# POWER_SUPPLY.net
KiCad netlist of a schematic drawn in Altium Designer
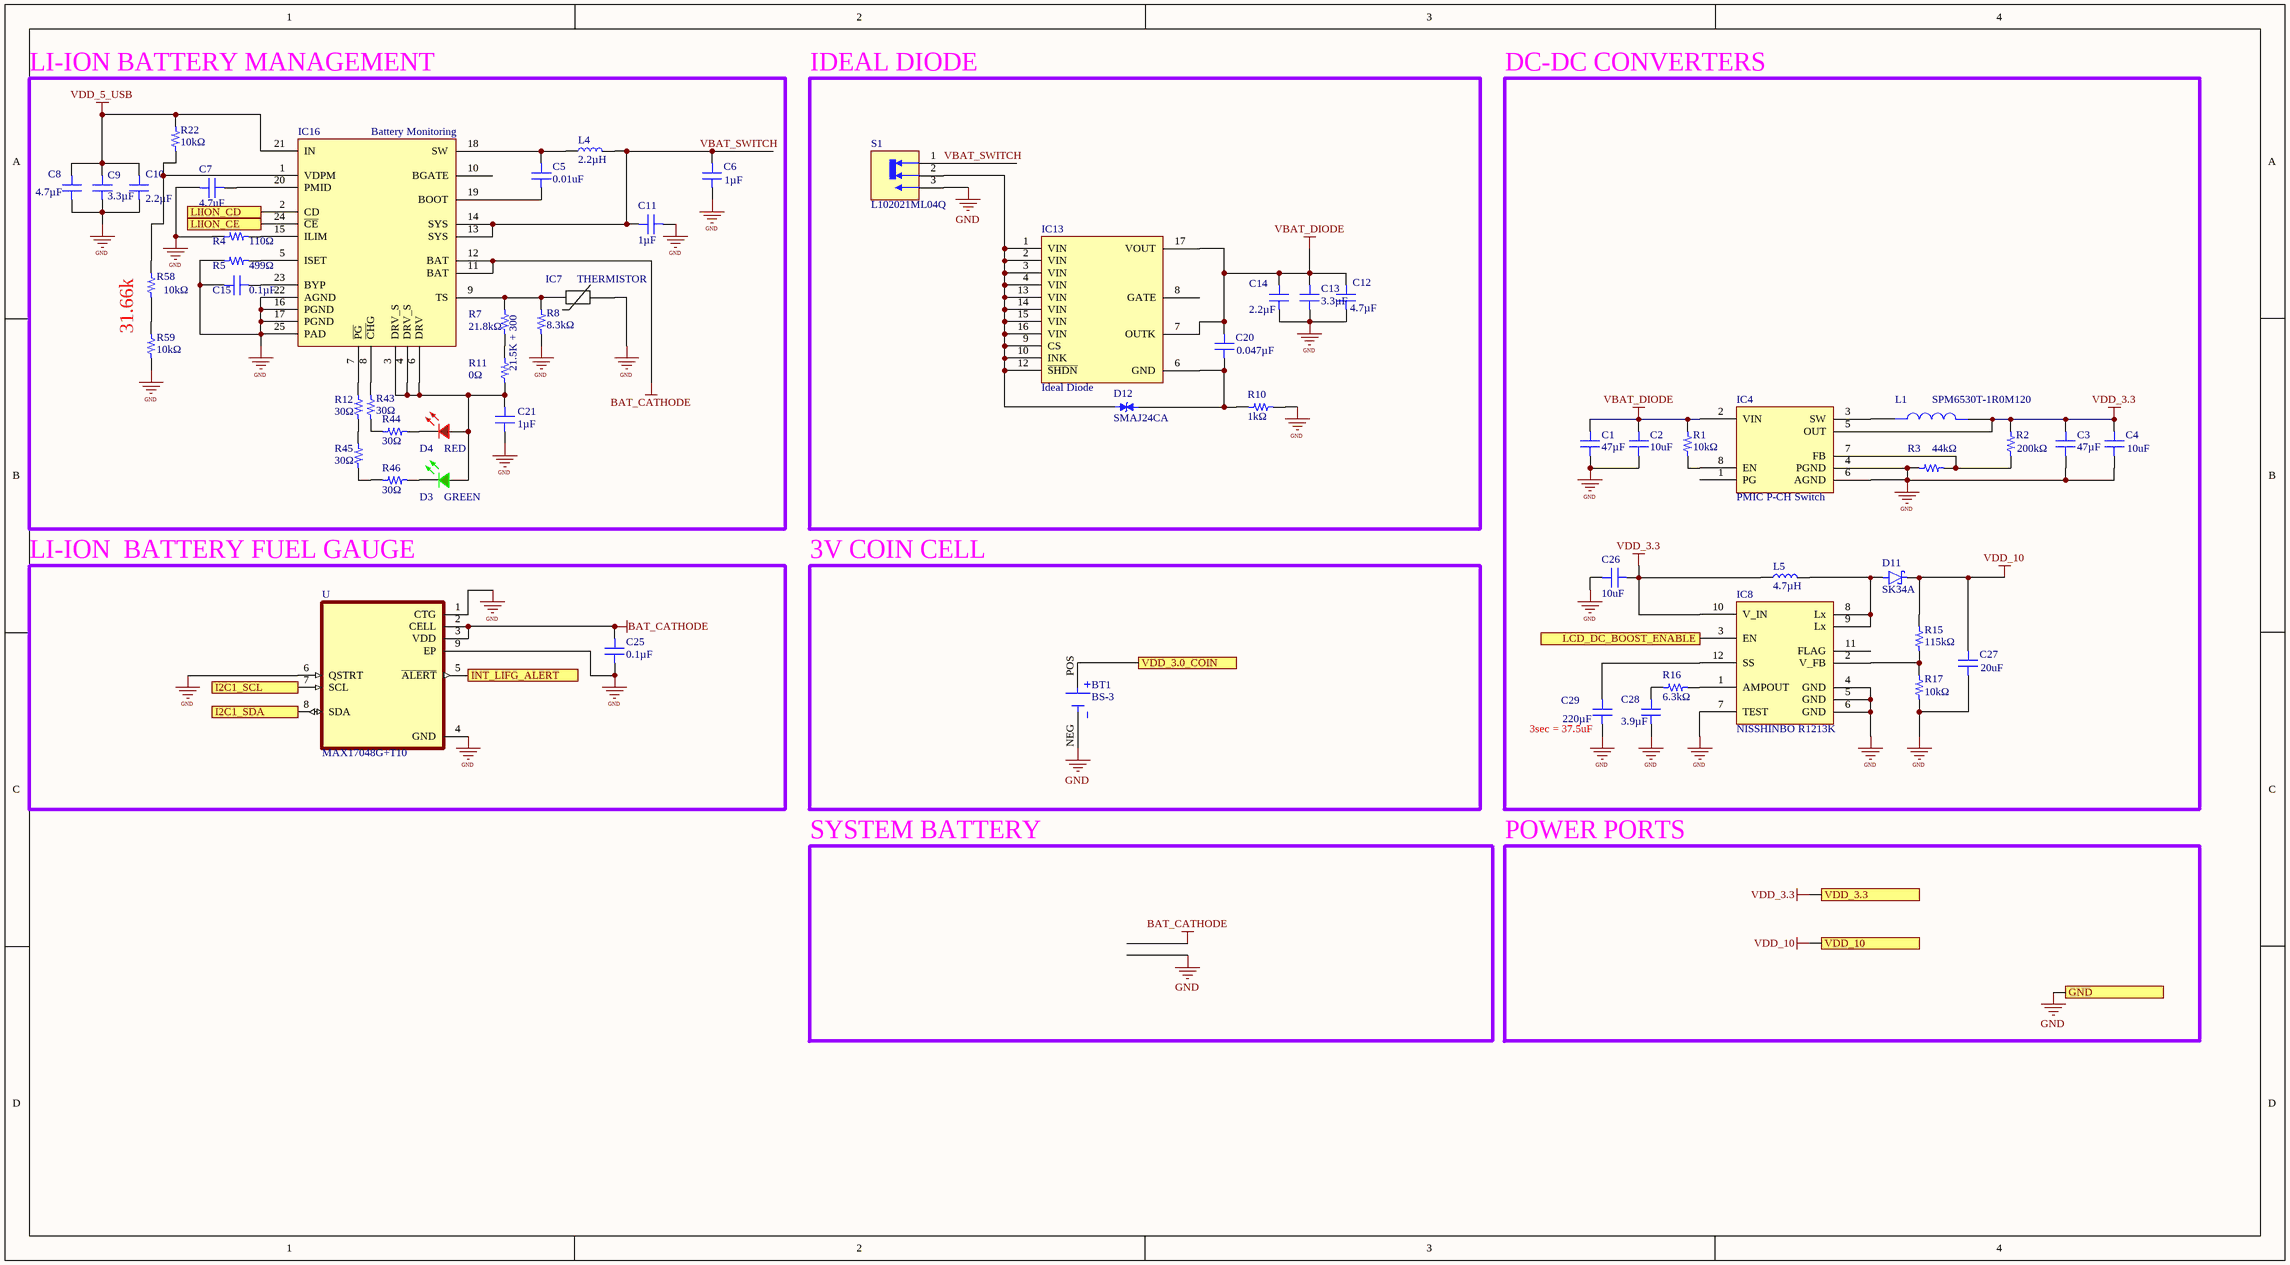
[diagram p0: POWER SUPPLY.SchDoc]

(export (version "E")
  (design (tool "Eeschema 10.0.6"))
  (components
    (comp (ref "BT1")
      (value "BS-3")
      (footprint "BAT_BS-3")
      (description "Holder Coincell 2032 Retainr Arm")
      (fields (field (name "MF") "MPD (Memory"))
      (libsource (lib "BS-3") (part "BS-3"))
    )
    (comp (ref "C1")
      (value "47µF")
      (footprint "CAP 1210_3225 - 2.2MM")
      (description "CAP CER 47UF 10V X7R 1210")
      (fields (field (name "MANUFACTURER") "Murata Electronics") (field (name "VOLTAGE") "10V"))
      (libsource (lib "MVVVMAltiumDatabase") (part "Capacitor"))
    )
    (comp (ref "C2")
      (value "10uF")
      (footprint "CAP 0603_1608")
      (description "CAP CER 10UF 6.3V X7R 0603")
      (fields (field (name "MANUFACTURER") "TDK") (field (name "VOLTAGE") "6.3V"))
      (libsource (lib "MVVVMAltiumDatabase") (part "Capacitor"))
    )
    (comp (ref "C3")
      (value "47µF")
      (footprint "CAP 1210_3225 - 2.2MM")
      (description "CAP CER 47UF 10V X7R 1210")
      (fields (field (name "MANUFACTURER") "Murata Electronics") (field (name "VOLTAGE") "10V"))
      (libsource (lib "MVVVMAltiumDatabase") (part "Capacitor"))
    )
    (comp (ref "C4")
      (value "10uF")
      (footprint "CAP 0603_1608")
      (description "CAP CER 10UF 6.3V X7R 0603")
      (fields (field (name "MANUFACTURER") "TDK") (field (name "VOLTAGE") "6.3V"))
      (libsource (lib "MVVVMAltiumDatabase") (part "Capacitor"))
    )
    (comp (ref "C5")
      (value "0.01uF")
      (footprint "CAP 0603_1608")
      (description "CAP CER 0.01UF 25V X7R 0603")
      (fields (field (name "MANUFACTURER") "TDK") (field (name "VOLTAGE") "25V"))
      (libsource (lib "MVVVMAltiumDatabase") (part "Capacitor"))
    )
    (comp (ref "C6")
      (value "1µF")
      (footprint "CAP 0603_1608")
      (description "CAP CER 1UF 10V X7R 0603")
      (fields (field (name "MANUFACTURER") "KEMET") (field (name "VOLTAGE") "10V"))
      (libsource (lib "MVVVMAltiumDatabase") (part "Capacitor"))
    )
    (comp (ref "C7")
      (value "4.7uF")
      (footprint "CAP 0603_1608")
      (description "CAP CER 4.7UF 50V X7R 0603")
      (fields (field (name "MANUFACTURER") "KEMET") (field (name "VOLTAGE") "25V"))
      (libsource (lib "MVVVMAltiumDatabase") (part "Capacitor"))
    )
    (comp (ref "C8")
      (value "4.7µF")
      (footprint "CAP 0805_2012")
      (description "CAP CER 4.7UF 16V X7R 0805")
      (fields (field (name "MANUFACTURER") "KEMET") (field (name "VOLTAGE") "16V"))
      (libsource (lib "MVVVMAltiumDatabase") (part "Capacitor"))
    )
    (comp (ref "C9")
      (value "3.3µF")
      (footprint "0805_2012 RF")
      (description "CAP CER 3.3UF 16V X7R 0805")
      (fields (field (name "MANUFACTURER") "KEMET") (field (name "VOLTAGE") "16V"))
      (libsource (lib "MVVVMAltiumDatabase") (part "Capacitor"))
    )
    (comp (ref "C10")
      (value "2.2µF")
      (footprint "CAP 0603_1608")
      (description "CAP CER 2.2UF 10V X7R 0603")
      (fields (field (name "MANUFACTURER") "KEMET") (field (name "VOLTAGE") "10V"))
      (libsource (lib "MVVVMAltiumDatabase") (part "Capacitor"))
    )
    (comp (ref "C11")
      (value "1µF")
      (footprint "CAP 0603_1608")
      (description "CAP CER 1UF 10V X7R 0603")
      (fields (field (name "MANUFACTURER") "KEMET") (field (name "VOLTAGE") "10V"))
      (libsource (lib "MVVVMAltiumDatabase") (part "Capacitor"))
    )
    (comp (ref "C12")
      (value "4.7µF")
      (footprint "CAP 0805_2012")
      (description "CAP CER 4.7UF 16V X7R 0805")
      (fields (field (name "MANUFACTURER") "KEMET") (field (name "VOLTAGE") "16V"))
      (libsource (lib "MVVVMAltiumDatabase") (part "Capacitor"))
    )
    (comp (ref "C13")
      (value "3.3µF")
      (footprint "0805_2012 RF")
      (description "CAP CER 3.3UF 16V X7R 0805")
      (fields (field (name "MANUFACTURER") "KEMET") (field (name "VOLTAGE") "16V"))
      (libsource (lib "MVVVMAltiumDatabase") (part "Capacitor"))
    )
    (comp (ref "C14")
      (value "2.2µF")
      (footprint "CAP 0603_1608")
      (description "CAP CER 2.2UF 10V X7R 0603")
      (fields (field (name "MANUFACTURER") "KEMET") (field (name "VOLTAGE") "10V"))
      (libsource (lib "MVVVMAltiumDatabase") (part "Capacitor"))
    )
    (comp (ref "C15")
      (value "0.1µF")
      (footprint "CAP 0603_1608 RF")
      (description "CAP CER 0.1UF 16V X7R 0603")
      (fields (field (name "MANUFACTURER") "KEMET") (field (name "VOLTAGE") "16V"))
      (libsource (lib "MVVVMAltiumDatabase") (part "Capacitor"))
    )
    (comp (ref "C20")
      (value "0.047µF")
      (footprint "CAP 0603_1608")
      (description "CAP CER 0.047UF 50V X7R 0603")
      (fields (field (name "MANUFACTURER") "KEMET") (field (name "VOLTAGE") "50V"))
      (libsource (lib "MVVVMAltiumDatabase") (part "Capacitor"))
    )
    (comp (ref "C21")
      (value "1µF")
      (footprint "CAP 0603_1608")
      (description "CAP CER 1UF 10V X7R 0603")
      (fields (field (name "MANUFACTURER") "KEMET") (field (name "VOLTAGE") "10V"))
      (libsource (lib "MVVVMAltiumDatabase") (part "Capacitor"))
    )
    (comp (ref "C25")
      (value "0.1µF")
      (footprint "CAP 0603_1608 RF")
      (description "CAP CER 0.1UF 16V X7R 0603")
      (fields (field (name "MANUFACTURER") "KEMET") (field (name "VOLTAGE") "16V"))
      (libsource (lib "MVVVMAltiumDatabase") (part "Capacitor"))
    )
    (comp (ref "C26")
      (value "10uF")
      (footprint "CAP 0603_1608")
      (description "CAP CER 10UF 6.3V X7R 0603")
      (fields (field (name "MANUFACTURER") "TDK") (field (name "VOLTAGE") "6.3V"))
      (libsource (lib "MVVVMAltiumDatabase") (part "Capacitor"))
    )
    (comp (ref "C27")
      (value "20uF")
      (footprint "CAP 0603_1608")
      (description "CAP CER 20UF 25V X7R 0603")
      (fields (field (name "MANUFACTURER") "TDK") (field (name "VOLTAGE") "25V"))
      (libsource (lib "MVVVMAltiumDatabase") (part "Capacitor"))
    )
    (comp (ref "C28")
      (value "3.9µF")
      (footprint "CAP 0805_2012")
      (description "CAP CER 3.9UF 50V X7R 0805")
      (fields (field (name "MANUFACTURER") "KEMET") (field (name "VOLTAGE") "50V"))
      (libsource (lib "MVVVMAltiumDatabase") (part "Capacitor"))
    )
    (comp (ref "C29")
      (value "220µF")
      (footprint "CAP 0805_2012")
      (description "CAP CER 220UF 50V X7R 0805")
      (fields (field (name "MANUFACTURER") "KEMET") (field (name "VOLTAGE") "50V"))
      (libsource (lib "MVVVMAltiumDatabase") (part "Capacitor"))
    )
    (comp (ref "D3")
      (value "GREEN")
      (footprint "LED 0603_1608")
      (description "LED RED CLEAR 0603 SMD")
      (fields (field (name "MANUFACTURER") "Würth Elektronik"))
      (libsource (lib "MVVVMAltiumDatabase") (part "LED_GREEN"))
    )
    (comp (ref "D4")
      (value "RED")
      (footprint "LED 0603_1608")
      (description "LED RED CLEAR 0603 SMD")
      (fields (field (name "MANUFACTURER") "Würth Elektronik"))
      (libsource (lib "MVVVMAltiumDatabase") (part "LED_RED"))
    )
    (comp (ref "D11") (value "SK34A") (footprint "DIOM4325X250N") (libsource (lib "SK34A") (part "SK34A")))
    (comp (ref "D12")
      (value "SMAJ24CA")
      (footprint "DIOM4325X250N")
      (libsource (lib "SMAJ24CA") (part "SMAJ24CA"))
    )
    (comp (ref "IC4")
      (value "PMIC P-CH Switch")
      (footprint "MPS MP2144 TSOT23-8")
      (description "IC PWR SWITCH P-CHAN 1:1 4TDFN")
      (fields (field (name "MANUFACTURER") "Vishay Siliconix"))
      (libsource (lib "MVVVMAltiumDatabase") (part "MPS MP2144"))
    )
    (comp (ref "IC7")
      (value "THERMISTOR")
      (footprint "THERMISTOR 2TH")
      (description "10kΩ THERMISTOR 0603")
      (fields (field (name "MANUFACTURER") "Texas Instruments"))
      (libsource (lib "MVVVMAltiumDatabase") (part "THERMISTOR"))
    )
    (comp (ref "IC8")
      (value "NISSHINBO R1213K")
      (footprint "NISSHINBO R1213K")
      (description "IC REG CONV BLUETTH 1OUT 12WSON")
      (fields (field (name "MANUFACTURER") "Texas Instruments"))
      (libsource (lib "MVVVMAltiumDatabase") (part "NISSHINBO R1213K"))
    )
    (comp (ref "IC13")
      (value "Ideal Diode")
      (footprint "ANALOG DFN-16")
      (description "IC OR CTRLR IDEAL DIODE SC70-6")
      (fields (field (name "MANUFACTURER") "Texas Instruments"))
      (libsource (lib "MVVVMAltiumDatabase") (part "ANALOG LTC4376"))
    )
    (comp (ref "IC16")
      (value "Battery Monitoring")
      (footprint "TI BQ24278")
      (description "IC BATT MON LI-ION 1CELL 24QFN")
      (fields (field (name "MANUFACTURER") "Analog Devices Inc."))
      (libsource (lib "MVVVMAltiumDatabase") (part "TI BQ24278"))
    )
    (comp (ref "L1")
      (value "SPM6530T-1R0M120")
      (footprint "IND_SPM6530T-1R0M120")
      (description "1 ÂµH Shielded Drum Core, Wirewound Inductor 13 A 7.81mOhm Max Nonstandard")
      (fields (field (name "MF") "TDK"))
      (libsource (lib "SPM6530T-1R0M120") (part "SPM6530T-1R0M120"))
    )
    (comp (ref "L4")
      (value "2.2µH")
      (footprint "IND 0806_2016")
      (description "FIXED IND 2.2UH 1.8A 139 MOHM")
      (fields (field (name "MANUFACTURER") "Samsung Electro-Mechanics") (field (name "TOLERANCE") "±20%"))
      (libsource (lib "MVVVMAltiumDatabase") (part "Inductor_2"))
    )
    (comp (ref "L5")
      (value "4.7µH")
      (footprint "NTC 0603_1608")
      (description "FIXED IND 4.7UH 16V")
      (fields (field (name "MANUFACTURER") "TDK Corporation") (field (name "TOLERANCE") "±20%"))
      (libsource (lib "MVVVMAltiumDatabase") (part "Inductor_2"))
    )
    (comp (ref "R1")
      (value "10kΩ")
      (footprint "RES 0603_1608 RF")
      (description "RES 10k OHM 1% 1/10W 0603")
      (fields (field (name "MANUFACTURER") "Vishay Dale") (field (name "TOLERANCE") "±1%"))
      (libsource (lib "MVVVMAltiumDatabase") (part "Resistor"))
    )
    (comp (ref "R2")
      (value "200kΩ")
      (footprint "RES 0603_1608 RF")
      (description "RES 200k OHM 1% 1/10W 0603")
      (fields (field (name "MANUFACTURER") "Vishay Dale") (field (name "TOLERANCE") "±1%"))
      (libsource (lib "MVVVMAltiumDatabase") (part "Resistor"))
    )
    (comp (ref "R3")
      (value "44kΩ")
      (footprint "RES 0603_1608 RF")
      (description "RES 44k OHM 1% 1/10W 0603")
      (fields (field (name "MANUFACTURER") "Vishay Dale") (field (name "TOLERANCE") "±1%"))
      (libsource (lib "MVVVMAltiumDatabase") (part "Resistor"))
    )
    (comp (ref "R4")
      (value "110Ω")
      (footprint "RES 0603_1608 RF")
      (description "RES 110 OHM 1% 1/10W 0603")
      (fields (field (name "MANUFACTURER") "Vishay Dale") (field (name "TOLERANCE") "±1%"))
      (libsource (lib "MVVVMAltiumDatabase") (part "Resistor"))
    )
    (comp (ref "R5")
      (value "499Ω")
      (footprint "RES 0603_1608 RF")
      (description "RES SMD 499 OHM 1% 1/10W 0603")
      (fields (field (name "MANUFACTURER") "Vishay Dale") (field (name "TOLERANCE") "±1%"))
      (libsource (lib "MVVVMAltiumDatabase") (part "Resistor"))
    )
    (comp (ref "R7")
      (value "21.8kΩ")
      (footprint "RES 0603_1608 RF")
      (description "RES 21.8k OHM 1% 1/10W 0603")
      (fields (field (name "MANUFACTURER") "Vishay Dale") (field (name "TOLERANCE") "±1%"))
      (libsource (lib "MVVVMAltiumDatabase") (part "Resistor"))
    )
    (comp (ref "R8")
      (value "8.3kΩ")
      (footprint "RES 0603_1608 RF")
      (description "RES 8.3k OHM 1% 1/10W 0603")
      (fields (field (name "MANUFACTURER") "Vishay Dale") (field (name "TOLERANCE") "±1%"))
      (libsource (lib "MVVVMAltiumDatabase") (part "Resistor"))
    )
    (comp (ref "R10")
      (value "1kΩ")
      (footprint "RES 0603_1608 RF")
      (description "RES SMD 1K OHM 0.1% 1/10W 0603")
      (fields (field (name "MANUFACTURER") "Susumu") (field (name "TOLERANCE") "±0.1%"))
      (libsource (lib "MVVVMAltiumDatabase") (part "Resistor"))
    )
    (comp (ref "R11")
      (value "0Ω")
      (footprint "RES 0603_1608 RF")
      (description "RES 0 OHM 1% 1/10W 0603")
      (fields (field (name "MANUFACTURER") "Vishay Dale") (field (name "TOLERANCE") "±1%"))
      (libsource (lib "MVVVMAltiumDatabase") (part "Resistor"))
    )
    (comp (ref "R12")
      (value "30Ω")
      (footprint "RES 0603_1608 RF")
      (description "RES 30 OHM 1% 1/10W 0603")
      (fields (field (name "MANUFACTURER") "Vishay Dale") (field (name "TOLERANCE") "±1%"))
      (libsource (lib "MVVVMAltiumDatabase") (part "Resistor"))
    )
    (comp (ref "R15")
      (value "115kΩ")
      (footprint "RES 0603_1608 RF")
      (description "RES 115k OHM 1% 1/10W 0603")
      (fields (field (name "MANUFACTURER") "Vishay Dale") (field (name "TOLERANCE") "±1%"))
      (libsource (lib "MVVVMAltiumDatabase") (part "Resistor"))
    )
    (comp (ref "R16")
      (value "6.3kΩ")
      (footprint "RES 0603_1608 RF")
      (description "RES 6.3k OHM 1% 1/10W 0603")
      (fields (field (name "MANUFACTURER") "Vishay Dale") (field (name "TOLERANCE") "±1%"))
      (libsource (lib "MVVVMAltiumDatabase") (part "Resistor"))
    )
    (comp (ref "R17")
      (value "10kΩ")
      (footprint "RES 0603_1608 RF")
      (description "RES 10k OHM 1% 1/10W 0603")
      (fields (field (name "MANUFACTURER") "Vishay Dale") (field (name "TOLERANCE") "±1%"))
      (libsource (lib "MVVVMAltiumDatabase") (part "Resistor"))
    )
    (comp (ref "R22")
      (value "10kΩ")
      (footprint "RES 0603_1608 RF")
      (description "RES 10k OHM 1% 1/10W 0603")
      (fields (field (name "MANUFACTURER") "Vishay Dale") (field (name "TOLERANCE") "±1%"))
      (libsource (lib "MVVVMAltiumDatabase") (part "Resistor"))
    )
    (comp (ref "R43")
      (value "30Ω")
      (footprint "RES 0603_1608 RF")
      (description "RES 30 OHM 1% 1/10W 0603")
      (fields (field (name "MANUFACTURER") "Vishay Dale") (field (name "TOLERANCE") "±1%"))
      (libsource (lib "MVVVMAltiumDatabase") (part "Resistor"))
    )
    (comp (ref "R44")
      (value "30Ω")
      (footprint "RES 0603_1608 RF")
      (description "RES 30 OHM 1% 1/10W 0603")
      (fields (field (name "MANUFACTURER") "Vishay Dale") (field (name "TOLERANCE") "±1%"))
      (libsource (lib "MVVVMAltiumDatabase") (part "Resistor"))
    )
    (comp (ref "R45")
      (value "30Ω")
      (footprint "RES 0603_1608 RF")
      (description "RES 30 OHM 1% 1/10W 0603")
      (fields (field (name "MANUFACTURER") "Vishay Dale") (field (name "TOLERANCE") "±1%"))
      (libsource (lib "MVVVMAltiumDatabase") (part "Resistor"))
    )
    (comp (ref "R46")
      (value "30Ω")
      (footprint "RES 0603_1608 RF")
      (description "RES 30 OHM 1% 1/10W 0603")
      (fields (field (name "MANUFACTURER") "Vishay Dale") (field (name "TOLERANCE") "±1%"))
      (libsource (lib "MVVVMAltiumDatabase") (part "Resistor"))
    )
    (comp (ref "R58")
      (value "10kΩ")
      (footprint "RES 0603_1608 RF")
      (description "RES 10k OHM 1% 1/10W 0603")
      (fields (field (name "MANUFACTURER") "Vishay Dale") (field (name "TOLERANCE") "±1%"))
      (libsource (lib "MVVVMAltiumDatabase") (part "Resistor"))
    )
    (comp (ref "R59")
      (value "10kΩ")
      (footprint "RES 0603_1608 RF")
      (description "RES 10k OHM 1% 1/10W 0603")
      (fields (field (name "MANUFACTURER") "Vishay Dale") (field (name "TOLERANCE") "±1%"))
      (libsource (lib "MVVVMAltiumDatabase") (part "Resistor"))
    )
    (comp (ref "S1")
      (value "L102021ML04Q")
      (footprint "SW_L102021ML04Q")
      (description "Slide Switch SPDT Through Hole, Right Angle")
      (fields (field (name "MF") "C&K"))
      (libsource (lib "L102021ML04Q") (part "L102021ML04Q"))
    )
    (comp (ref "U")
      (value "MAX17048G+T10")
      (footprint "SON50P200X200X80-9N")
      (description "Battery Battery Monitor IC Lithium-Ion 8-TDFN-EP (2x2)")
      (fields
        (field (name "MF") "Maxim Integrated")
        (field (name "DIGI-KEY_PART_NUMBER") "MAX17048G+T10CT-ND")
      )
      (libsource (lib "MAX17048G_T10") (part "MAX17048G+T10"))
    )
  )
  (nets
    (net (code "1") (name "/I2C1_SCL") (class "Default")
      (node (ref "U") (pin "7") (pinfunction "SCL_7") (pintype "input"))
    )
    (net (code "2") (name "/I2C1_SDA") (class "Default")
      (node (ref "U") (pin "8") (pinfunction "SDA_8") (pintype "bidirectional"))
    )
    (net (code "3") (name "/INT_LIFG_ALERT") (class "Default")
      (node (ref "U") (pin "5") (pinfunction "~{ALERT}_5") (pintype "output"))
    )
    (net (code "4") (name "/LCD_DC_BOOST_ENABLE") (class "Default")
      (node (ref "IC8") (pin "3") (pinfunction "EN_3") (pintype "passive"))
    )
    (net (code "5") (name "/LIION_CD") (class "Default")
      (node (ref "IC16") (pin "2") (pinfunction "CD_2") (pintype "passive"))
    )
    (net (code "6") (name "/LIION_CE") (class "Default")
      (node (ref "IC16") (pin "24") (pinfunction "~{CE}_24") (pintype "passive"))
    )
    (net (code "7") (name "/VBAT_SWITCH") (class "Default")
      (node (ref "C11") (pin "2") (pinfunction "2_2") (pintype "passive"))
      (node (ref "C6") (pin "2") (pinfunction "2_2") (pintype "passive"))
      (node (ref "IC16") (pin "13") (pinfunction "SYS_13") (pintype "passive"))
      (node (ref "IC16") (pin "14") (pinfunction "SYS_14") (pintype "passive"))
      (node (ref "L4") (pin "2") (pinfunction "2_2") (pintype "passive"))
      (node (ref "S1") (pin "1") (pinfunction "1_1") (pintype "passive"))
    )
    (net (code "8") (name "/VDD_3.0_COIN") (class "Default")
      (node (ref "BT1") (pin "POS") (pinfunction "POS_POS") (pintype "passive"))
    )
    (net (code "9") (name "BAT_CATHODE") (class "Default")
      (node (ref "C25") (pin "2") (pinfunction "2_2") (pintype "passive"))
      (node (ref "IC16") (pin "11") (pinfunction "BAT_11") (pintype "passive"))
      (node (ref "IC16") (pin "12") (pinfunction "BAT_12") (pintype "passive"))
      (node (ref "U") (pin "2") (pinfunction "CELL_2") (pintype "power_in"))
      (node (ref "U") (pin "3") (pinfunction "VDD_3") (pintype "power_in"))
    )
    (net (code "10") (name "GND") (class "Default")
      (node (ref "BT1") (pin "NEG") (pinfunction "NEG_NEG") (pintype "passive"))
      (node (ref "C1") (pin "1") (pinfunction "1_1") (pintype "passive"))
      (node (ref "C10") (pin "1") (pinfunction "1_1") (pintype "passive"))
      (node (ref "C11") (pin "1") (pinfunction "1_1") (pintype "passive"))
      (node (ref "C12") (pin "1") (pinfunction "1_1") (pintype "passive"))
      (node (ref "C13") (pin "1") (pinfunction "1_1") (pintype "passive"))
      (node (ref "C14") (pin "1") (pinfunction "1_1") (pintype "passive"))
      (node (ref "C15") (pin "1") (pinfunction "1_1") (pintype "passive"))
      (node (ref "C2") (pin "1") (pinfunction "1_1") (pintype "passive"))
      (node (ref "C21") (pin "1") (pinfunction "1_1") (pintype "passive"))
      (node (ref "C25") (pin "1") (pinfunction "1_1") (pintype "passive"))
      (node (ref "C26") (pin "1") (pinfunction "1_1") (pintype "passive"))
      (node (ref "C27") (pin "1") (pinfunction "1_1") (pintype "passive"))
      (node (ref "C28") (pin "1") (pinfunction "1_1") (pintype "passive"))
      (node (ref "C29") (pin "1") (pinfunction "1_1") (pintype "passive"))
      (node (ref "C3") (pin "1") (pinfunction "1_1") (pintype "passive"))
      (node (ref "C4") (pin "1") (pinfunction "1_1") (pintype "passive"))
      (node (ref "C6") (pin "1") (pinfunction "1_1") (pintype "passive"))
      (node (ref "C7") (pin "2") (pinfunction "2_2") (pintype "passive"))
      (node (ref "C8") (pin "1") (pinfunction "1_1") (pintype "passive"))
      (node (ref "C9") (pin "1") (pinfunction "1_1") (pintype "passive"))
      (node (ref "IC16") (pin "16") (pinfunction "PGND_16") (pintype "passive"))
      (node (ref "IC16") (pin "17") (pinfunction "PGND_17") (pintype "passive"))
      (node (ref "IC16") (pin "22") (pinfunction "AGND_22") (pintype "passive"))
      (node (ref "IC16") (pin "25") (pinfunction "PAD_25") (pintype "passive"))
      (node (ref "IC4") (pin "4") (pinfunction "PGND_4") (pintype "passive"))
      (node (ref "IC4") (pin "6") (pinfunction "AGND_6") (pintype "passive"))
      (node (ref "IC7") (pin "2") (pinfunction "2_2") (pintype "passive"))
      (node (ref "IC8") (pin "4") (pinfunction "GND_4") (pintype "passive"))
      (node (ref "IC8") (pin "5") (pinfunction "GND_5") (pintype "passive"))
      (node (ref "IC8") (pin "6") (pinfunction "GND_6") (pintype "passive"))
      (node (ref "IC8") (pin "7") (pinfunction "TEST_7") (pintype "passive"))
      (node (ref "R10") (pin "1") (pinfunction "1_1") (pintype "passive"))
      (node (ref "R17") (pin "1") (pinfunction "1_1") (pintype "passive"))
      (node (ref "R3") (pin "1") (pinfunction "1_1") (pintype "passive"))
      (node (ref "R4") (pin "1") (pinfunction "1_1") (pintype "passive"))
      (node (ref "R5") (pin "1") (pinfunction "1_1") (pintype "passive"))
      (node (ref "R59") (pin "2") (pinfunction "2_2") (pintype "passive"))
      (node (ref "R8") (pin "2") (pinfunction "2_2") (pintype "passive"))
      (node (ref "S1") (pin "3") (pinfunction "3_3") (pintype "passive"))
      (node (ref "U") (pin "1") (pinfunction "CTG_1") (pintype "power_in"))
      (node (ref "U") (pin "4") (pinfunction "GND_4") (pintype "power_in"))
      (node (ref "U") (pin "6") (pinfunction "QSTRT_6") (pintype "input"))
      (node (ref "U") (pin "9") (pinfunction "EP_9") (pintype "power_in"))
    )
    (net (code "11") (name "Net-(C28-Pad2)") (class "Default")
      (node (ref "C28") (pin "2") (pinfunction "2_2") (pintype "passive"))
      (node (ref "R16") (pin "1") (pinfunction "1_1") (pintype "passive"))
    )
    (net (code "12") (name "Net-(D3-Pad2)") (class "Default")
      (node (ref "D3") (pin "2") (pinfunction "2_2") (pintype "passive"))
      (node (ref "R46") (pin "1") (pinfunction "1_1") (pintype "passive"))
    )
    (net (code "13") (name "Net-(D4-Pad2)") (class "Default")
      (node (ref "D4") (pin "2") (pinfunction "2_2") (pintype "passive"))
      (node (ref "R44") (pin "1") (pinfunction "1_1") (pintype "passive"))
    )
    (net (code "14") (name "Net-(D11-PadA)") (class "Default")
      (node (ref "D11") (pin "A") (pinfunction "A_A") (pintype "passive"))
      (node (ref "IC8") (pin "8") (pinfunction "Lx_8") (pintype "passive"))
      (node (ref "IC8") (pin "9") (pinfunction "Lx_9") (pintype "passive"))
      (node (ref "L5") (pin "2") (pinfunction "2_2") (pintype "passive"))
    )
    (net (code "15") (name "Net-(IC4-EN)") (class "Default")
      (node (ref "IC4") (pin "8") (pinfunction "EN_8") (pintype "passive"))
      (node (ref "R1") (pin "1") (pinfunction "1_1") (pintype "passive"))
    )
    (net (code "16") (name "Net-(IC4-FB)") (class "Default")
      (node (ref "IC4") (pin "7") (pinfunction "FB_7") (pintype "passive"))
      (node (ref "R2") (pin "1") (pinfunction "1_1") (pintype "passive"))
      (node (ref "R3") (pin "2") (pinfunction "2_2") (pintype "passive"))
    )
    (net (code "17") (name "Net-(IC4-SW)") (class "Default")
      (node (ref "IC4") (pin "3") (pinfunction "SW_3") (pintype "passive"))
      (node (ref "L1") (pin "1") (pinfunction "1_1") (pintype "passive"))
    )
    (net (code "18") (name "Net-(IC8-AMPOUT)") (class "Default")
      (node (ref "IC8") (pin "1") (pinfunction "AMPOUT_1") (pintype "passive"))
      (node (ref "R16") (pin "2") (pinfunction "2_2") (pintype "passive"))
    )
    (net (code "19") (name "Net-(IC8-SS)") (class "Default")
      (node (ref "C29") (pin "2") (pinfunction "2_2") (pintype "passive"))
      (node (ref "IC8") (pin "12") (pinfunction "SS_12") (pintype "passive"))
    )
    (net (code "20") (name "Net-(IC8-V_FB)") (class "Default")
      (node (ref "IC8") (pin "2") (pinfunction "V_FB_2") (pintype "passive"))
      (node (ref "R15") (pin "1") (pinfunction "1_1") (pintype "passive"))
      (node (ref "R17") (pin "2") (pinfunction "2_2") (pintype "passive"))
    )
    (net (code "21") (name "Net-(IC13-CS)") (class "Default")
      (node (ref "D12") (pin "1") (pinfunction "1_1") (pintype "passive"))
      (node (ref "IC13") (pin "1") (pinfunction "VIN_1") (pintype "passive"))
      (node (ref "IC13") (pin "10") (pinfunction "INK_10") (pintype "passive"))
      (node (ref "IC13") (pin "12") (pinfunction "~{SHDN}_12") (pintype "passive"))
      (node (ref "IC13") (pin "13") (pinfunction "VIN_13") (pintype "passive"))
      (node (ref "IC13") (pin "14") (pinfunction "VIN_14") (pintype "passive"))
      (node (ref "IC13") (pin "15") (pinfunction "VIN_15") (pintype "passive"))
      (node (ref "IC13") (pin "16") (pinfunction "VIN_16") (pintype "passive"))
      (node (ref "IC13") (pin "2") (pinfunction "VIN_2") (pintype "passive"))
      (node (ref "IC13") (pin "3") (pinfunction "VIN_3") (pintype "passive"))
      (node (ref "IC13") (pin "4") (pinfunction "VIN_4") (pintype "passive"))
      (node (ref "IC13") (pin "9") (pinfunction "CS_9") (pintype "passive"))
      (node (ref "S1") (pin "2") (pinfunction "2_2") (pintype "passive"))
    )
    (net (code "22") (name "Net-(IC13-GND)") (class "Default")
      (node (ref "C20") (pin "1") (pinfunction "1_1") (pintype "passive"))
      (node (ref "D12") (pin "2") (pinfunction "2_2") (pintype "passive"))
      (node (ref "IC13") (pin "6") (pinfunction "GND_6") (pintype "passive"))
      (node (ref "R10") (pin "2") (pinfunction "2_2") (pintype "passive"))
    )
    (net (code "23") (name "Net-(IC16-BOOT)") (class "Default")
      (node (ref "C5") (pin "1") (pinfunction "1_1") (pintype "passive"))
      (node (ref "IC16") (pin "19") (pinfunction "BOOT_19") (pintype "passive"))
    )
    (net (code "24") (name "Net-(IC16-BYP)") (class "Default")
      (node (ref "C15") (pin "2") (pinfunction "2_2") (pintype "passive"))
      (node (ref "IC16") (pin "23") (pinfunction "BYP_23") (pintype "passive"))
    )
    (net (code "25") (name "Net-(IC16-DRV)") (class "Default")
      (node (ref "C21") (pin "2") (pinfunction "2_2") (pintype "passive"))
      (node (ref "D3") (pin "1") (pinfunction "1_1") (pintype "passive"))
      (node (ref "D4") (pin "1") (pinfunction "1_1") (pintype "passive"))
      (node (ref "IC16") (pin "3") (pinfunction "DRV_S_3") (pintype "passive"))
      (node (ref "IC16") (pin "4") (pinfunction "DRV_S_4") (pintype "passive"))
      (node (ref "IC16") (pin "6") (pinfunction "DRV_6") (pintype "passive"))
      (node (ref "R11") (pin "1") (pinfunction "1_1") (pintype "passive"))
    )
    (net (code "26") (name "Net-(IC16-ILIM)") (class "Default")
      (node (ref "IC16") (pin "15") (pinfunction "ILIM_15") (pintype "passive"))
      (node (ref "R4") (pin "2") (pinfunction "2_2") (pintype "passive"))
    )
    (net (code "27") (name "Net-(IC16-ISET)") (class "Default")
      (node (ref "IC16") (pin "5") (pinfunction "ISET_5") (pintype "passive"))
      (node (ref "R5") (pin "2") (pinfunction "2_2") (pintype "passive"))
    )
    (net (code "28") (name "Net-(IC16-PMID)") (class "Default")
      (node (ref "C7") (pin "1") (pinfunction "1_1") (pintype "passive"))
      (node (ref "IC16") (pin "20") (pinfunction "PMID_20") (pintype "passive"))
    )
    (net (code "29") (name "Net-(IC16-SW)") (class "Default")
      (node (ref "C5") (pin "2") (pinfunction "2_2") (pintype "passive"))
      (node (ref "IC16") (pin "18") (pinfunction "SW_18") (pintype "passive"))
      (node (ref "L4") (pin "1") (pinfunction "1_1") (pintype "passive"))
    )
    (net (code "30") (name "Net-(IC16-TS)") (class "Default")
      (node (ref "IC16") (pin "9") (pinfunction "TS_9") (pintype "passive"))
      (node (ref "IC7") (pin "1") (pinfunction "1_1") (pintype "passive"))
      (node (ref "R7") (pin "2") (pinfunction "2_2") (pintype "passive"))
      (node (ref "R8") (pin "1") (pinfunction "1_1") (pintype "passive"))
    )
    (net (code "31") (name "Net-(IC16-VDPM)") (class "Default")
      (node (ref "IC16") (pin "1") (pinfunction "VDPM_1") (pintype "passive"))
      (node (ref "R22") (pin "2") (pinfunction "2_2") (pintype "passive"))
      (node (ref "R58") (pin "2") (pinfunction "2_2") (pintype "passive"))
    )
    (net (code "32") (name "Net-(IC16-~{CH}G)") (class "Default")
      (node (ref "IC16") (pin "8") (pinfunction "~{CH}G_8") (pintype "passive"))
      (node (ref "R43") (pin "2") (pinfunction "2_2") (pintype "passive"))
    )
    (net (code "33") (name "Net-(IC16-~{PG})") (class "Default")
      (node (ref "IC16") (pin "7") (pinfunction "~{PG}_7") (pintype "passive"))
      (node (ref "R12") (pin "2") (pinfunction "2_2") (pintype "passive"))
    )
    (net (code "34") (name "Net-(R11-Pad2)") (class "Default")
      (node (ref "R11") (pin "2") (pinfunction "2_2") (pintype "passive"))
      (node (ref "R7") (pin "1") (pinfunction "1_1") (pintype "passive"))
    )
    (net (code "35") (name "Net-(R12-Pad1)") (class "Default")
      (node (ref "R12") (pin "1") (pinfunction "1_1") (pintype "passive"))
      (node (ref "R45") (pin "2") (pinfunction "2_2") (pintype "passive"))
    )
    (net (code "36") (name "Net-(R43-Pad1)") (class "Default")
      (node (ref "R43") (pin "1") (pinfunction "1_1") (pintype "passive"))
      (node (ref "R44") (pin "2") (pinfunction "2_2") (pintype "passive"))
    )
    (net (code "37") (name "Net-(R45-Pad1)") (class "Default")
      (node (ref "R45") (pin "1") (pinfunction "1_1") (pintype "passive"))
      (node (ref "R46") (pin "2") (pinfunction "2_2") (pintype "passive"))
    )
    (net (code "38") (name "Net-(R58-Pad1)") (class "Default")
      (node (ref "R58") (pin "1") (pinfunction "1_1") (pintype "passive"))
      (node (ref "R59") (pin "1") (pinfunction "1_1") (pintype "passive"))
    )
    (net (code "39") (name "VBAT_DIODE") (class "Default")
      (node (ref "C1") (pin "2") (pinfunction "2_2") (pintype "passive"))
      (node (ref "C12") (pin "2") (pinfunction "2_2") (pintype "passive"))
      (node (ref "C13") (pin "2") (pinfunction "2_2") (pintype "passive"))
      (node (ref "C14") (pin "2") (pinfunction "2_2") (pintype "passive"))
      (node (ref "C2") (pin "2") (pinfunction "2_2") (pintype "passive"))
      (node (ref "C20") (pin "2") (pinfunction "2_2") (pintype "passive"))
      (node (ref "IC13") (pin "17") (pinfunction "VOUT_17") (pintype "passive"))
      (node (ref "IC13") (pin "7") (pinfunction "OUTK_7") (pintype "passive"))
      (node (ref "IC4") (pin "2") (pinfunction "VIN_2") (pintype "passive"))
      (node (ref "R1") (pin "2") (pinfunction "2_2") (pintype "passive"))
    )
    (net (code "40") (name "VDD_3.3") (class "Default")
      (node (ref "C26") (pin "2") (pinfunction "2_2") (pintype "passive"))
      (node (ref "C3") (pin "2") (pinfunction "2_2") (pintype "passive"))
      (node (ref "C4") (pin "2") (pinfunction "2_2") (pintype "passive"))
      (node (ref "IC4") (pin "5") (pinfunction "OUT_5") (pintype "passive"))
      (node (ref "IC8") (pin "10") (pinfunction "V_IN_10") (pintype "passive"))
      (node (ref "L1") (pin "2") (pinfunction "2_2") (pintype "passive"))
      (node (ref "L5") (pin "1") (pinfunction "1_1") (pintype "passive"))
      (node (ref "R2") (pin "2") (pinfunction "2_2") (pintype "passive"))
    )
    (net (code "41") (name "VDD_5_USB") (class "Default")
      (node (ref "C10") (pin "2") (pinfunction "2_2") (pintype "passive"))
      (node (ref "C8") (pin "2") (pinfunction "2_2") (pintype "passive"))
      (node (ref "C9") (pin "2") (pinfunction "2_2") (pintype "passive"))
      (node (ref "IC16") (pin "21") (pinfunction "IN_21") (pintype "passive"))
      (node (ref "R22") (pin "1") (pinfunction "1_1") (pintype "passive"))
    )
    (net (code "42") (name "VDD_10") (class "Default")
      (node (ref "C27") (pin "2") (pinfunction "2_2") (pintype "passive"))
      (node (ref "D11") (pin "C") (pinfunction "K_C") (pintype "passive"))
      (node (ref "R15") (pin "2") (pinfunction "2_2") (pintype "passive"))
    )
    (net (code "43") (name "unconnected-(IC4-PG-Pad1)") (class "Default")
      (node (ref "IC4") (pin "1") (pinfunction "PG_1") (pintype "passive"))
    )
    (net (code "44") (name "unconnected-(IC8-FLAG-Pad11)") (class "Default")
      (node (ref "IC8") (pin "11") (pinfunction "FLAG_11") (pintype "passive"))
    )
    (net (code "45") (name "unconnected-(IC13-GATE-Pad8)") (class "Default")
      (node (ref "IC13") (pin "8") (pinfunction "GATE_8") (pintype "passive"))
    )
    (net (code "46") (name "unconnected-(IC16-BGATE-Pad10)") (class "Default")
      (node (ref "IC16") (pin "10") (pinfunction "BGATE_10") (pintype "passive"))
    )
  )
)
